# Bridge.net
KiCad netlist of a schematic drawn in Altium Designer
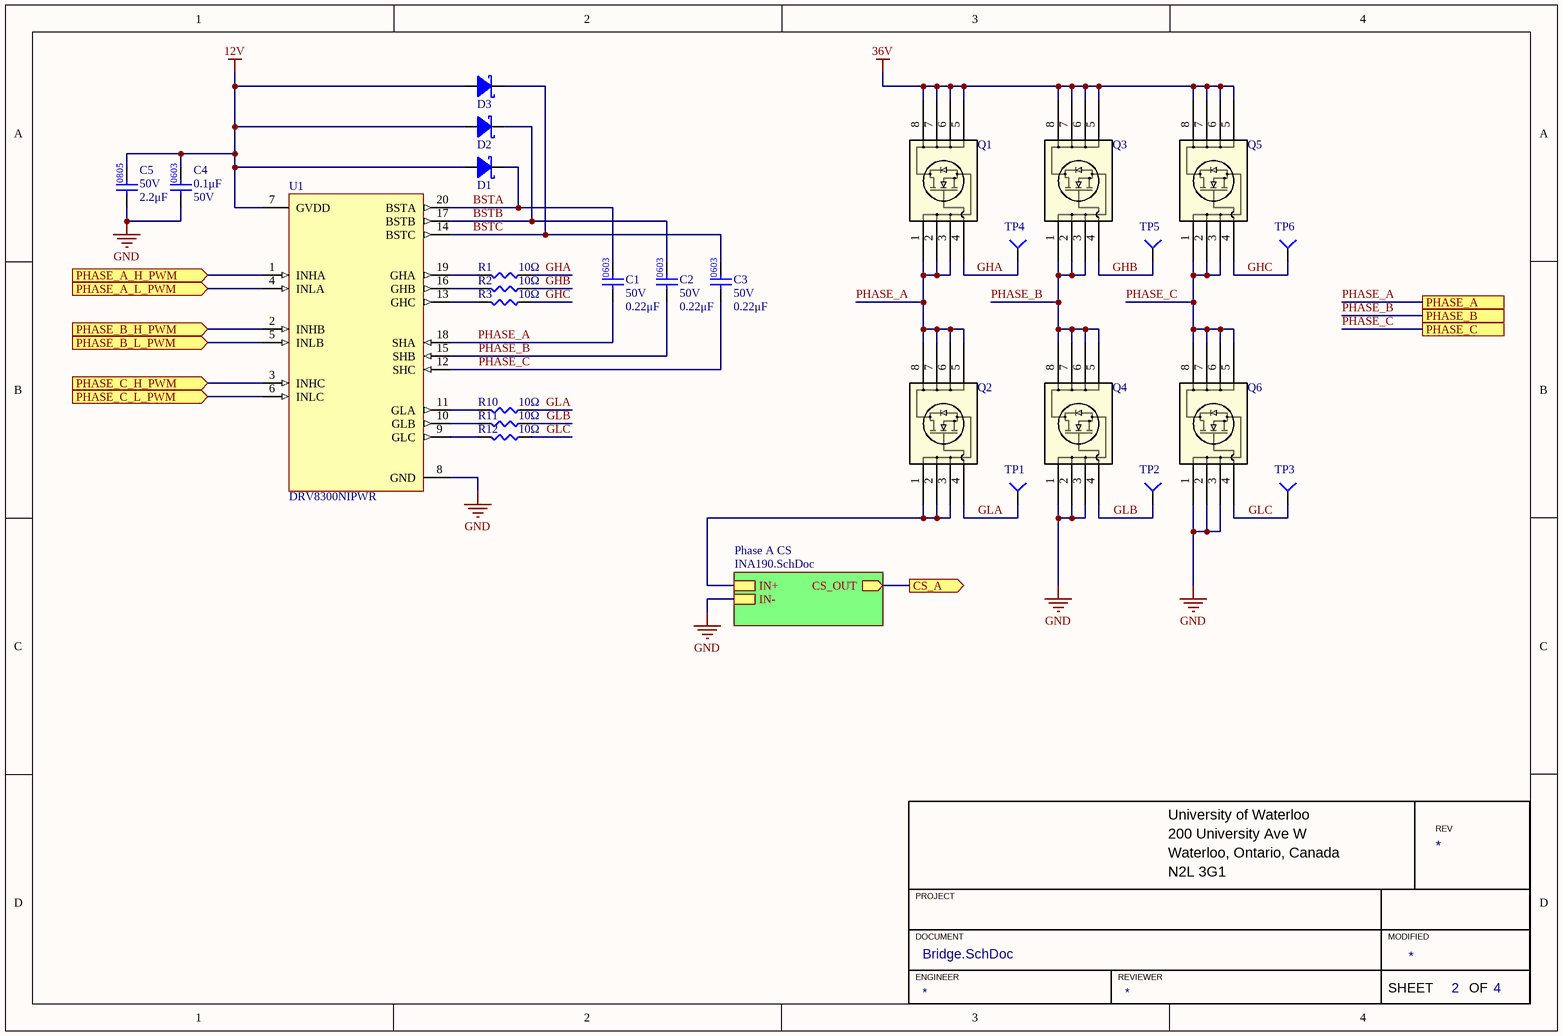
[diagram p0: Bridge.SchDoc]

(export (version "E")
  (design (tool "Eeschema 10.0.6"))
  (components
    (comp (ref "C1")
      (value "0.22μF")
      (footprint "CAP0603")
      (description "CAP CER 0.22UF 50V X7R 0603")
      (fields
        (field (name "VOLTAGE RATING") "50V")
        (field (name "LCSC PART #") "C5378")
        (field (name "Comment") "CAP_0.22uF_50V_0603")
      )
      (libsource (lib "UWRT_Schematic_Library_2020") (part "CAP_0.22uF_50V_0603"))
    )
    (comp (ref "C2")
      (value "0.22μF")
      (footprint "CAP0603")
      (description "CAP CER 0.22UF 50V X7R 0603")
      (fields
        (field (name "VOLTAGE RATING") "50V")
        (field (name "LCSC PART #") "C5378")
        (field (name "Comment") "CAP_0.22uF_50V_0603")
      )
      (libsource (lib "UWRT_Schematic_Library_2020") (part "CAP_0.22uF_50V_0603"))
    )
    (comp (ref "C3")
      (value "0.22μF")
      (footprint "CAP0603")
      (description "CAP CER 0.22UF 50V X7R 0603")
      (fields
        (field (name "VOLTAGE RATING") "50V")
        (field (name "LCSC PART #") "C5378")
        (field (name "Comment") "CAP_0.22uF_50V_0603")
      )
      (libsource (lib "UWRT_Schematic_Library_2020") (part "CAP_0.22uF_50V_0603"))
    )
    (comp (ref "C4")
      (value "0.1μF")
      (footprint "CAP0603")
      (description "CAP CER 0.1UF 50V X7R 0603")
      (fields (field (name "VOLTAGE RATING") "50V") (field (name "Comment") "CAP_0.1uF_50V_0603"))
      (libsource (lib "UWRT_Schematic_Library_2020") (part "CAP_0.1uF_50V_0603"))
    )
    (comp (ref "C5")
      (value "2.2μF")
      (footprint "CAP0805")
      (description "CAP CER 2.2UF 50V X5R 0805")
      (fields (field (name "VOLTAGE RATING") "50V") (field (name "Comment") "CAP_2.2uF_50V_0805"))
      (libsource (lib "UWRT_Schematic_Library_2020") (part "CAP_2.2uF_50V_0805"))
    )
    (comp (ref "D1")
      (value "DIO_SCHOTTKY_60V_2A")
      (footprint "SOD-123_FLAT")
      (description "DIODE SCHOTTKY 40V 520MA SOD323")
      (libsource (lib "Personal_Schematic_Library_2022") (part "DIO_SCHOTTKY_60V_2A"))
    )
    (comp (ref "D2")
      (value "DIO_SCHOTTKY_60V_2A")
      (footprint "SOD-123_FLAT")
      (description "DIODE SCHOTTKY 40V 520MA SOD323")
      (libsource (lib "Personal_Schematic_Library_2022") (part "DIO_SCHOTTKY_60V_2A"))
    )
    (comp (ref "D3")
      (value "DIO_SCHOTTKY_60V_2A")
      (footprint "SOD-123_FLAT")
      (description "DIODE SCHOTTKY 40V 520MA SOD323")
      (libsource (lib "Personal_Schematic_Library_2022") (part "DIO_SCHOTTKY_60V_2A"))
    )
    (comp (ref "Q1")
      (value "CSD19502Q5B")
      (footprint "DFN5060")
      (description "MOSFET N-CH 80V 100A 8VSON")
      (libsource (lib "UWRT_Schematic_Library_2020") (part "NMOS_CSD19502Q5B_80V_100A"))
    )
    (comp (ref "Q2")
      (value "CSD19502Q5B")
      (footprint "DFN5060")
      (description "MOSFET N-CH 80V 100A 8VSON")
      (libsource (lib "UWRT_Schematic_Library_2020") (part "NMOS_CSD19502Q5B_80V_100A"))
    )
    (comp (ref "Q3")
      (value "CSD19502Q5B")
      (footprint "DFN5060")
      (description "MOSFET N-CH 80V 100A 8VSON")
      (libsource (lib "UWRT_Schematic_Library_2020") (part "NMOS_CSD19502Q5B_80V_100A"))
    )
    (comp (ref "Q4")
      (value "CSD19502Q5B")
      (footprint "DFN5060")
      (description "MOSFET N-CH 80V 100A 8VSON")
      (libsource (lib "UWRT_Schematic_Library_2020") (part "NMOS_CSD19502Q5B_80V_100A"))
    )
    (comp (ref "Q5")
      (value "CSD19502Q5B")
      (footprint "DFN5060")
      (description "MOSFET N-CH 80V 100A 8VSON")
      (libsource (lib "UWRT_Schematic_Library_2020") (part "NMOS_CSD19502Q5B_80V_100A"))
    )
    (comp (ref "Q6")
      (value "CSD19502Q5B")
      (footprint "DFN5060")
      (description "MOSFET N-CH 80V 100A 8VSON")
      (libsource (lib "UWRT_Schematic_Library_2020") (part "NMOS_CSD19502Q5B_80V_100A"))
    )
    (comp (ref "R1")
      (value "10Ω")
      (footprint "RES0805")
      (description "RES 10 OHM 1% 1/8W 0805")
      (fields (field (name "LCSC PART #") "C17415") (field (name "Comment") "RES_10Ω_0805_1%"))
      (libsource (lib "UWRT_Schematic_Library_2020") (part "RES_10Ω_0805_1%"))
    )
    (comp (ref "R2")
      (value "10Ω")
      (footprint "RES0805")
      (description "RES 10 OHM 1% 1/8W 0805")
      (fields (field (name "LCSC PART #") "C17415") (field (name "Comment") "RES_10Ω_0805_1%"))
      (libsource (lib "UWRT_Schematic_Library_2020") (part "RES_10Ω_0805_1%"))
    )
    (comp (ref "R3")
      (value "10Ω")
      (footprint "RES0805")
      (description "RES 10 OHM 1% 1/8W 0805")
      (fields (field (name "LCSC PART #") "C17415") (field (name "Comment") "RES_10Ω_0805_1%"))
      (libsource (lib "UWRT_Schematic_Library_2020") (part "RES_10Ω_0805_1%"))
    )
    (comp (ref "R10")
      (value "10Ω")
      (footprint "RES0805")
      (description "RES 10 OHM 1% 1/8W 0805")
      (fields (field (name "LCSC PART #") "C17415") (field (name "Comment") "RES_10Ω_0805_1%"))
      (libsource (lib "UWRT_Schematic_Library_2020") (part "RES_10Ω_0805_1%"))
    )
    (comp (ref "R11")
      (value "10Ω")
      (footprint "RES0805")
      (description "RES 10 OHM 1% 1/8W 0805")
      (fields (field (name "LCSC PART #") "C17415") (field (name "Comment") "RES_10Ω_0805_1%"))
      (libsource (lib "UWRT_Schematic_Library_2020") (part "RES_10Ω_0805_1%"))
    )
    (comp (ref "R12")
      (value "10Ω")
      (footprint "RES0805")
      (description "RES 10 OHM 1% 1/8W 0805")
      (fields (field (name "LCSC PART #") "C17415") (field (name "Comment") "RES_10Ω_0805_1%"))
      (libsource (lib "UWRT_Schematic_Library_2020") (part "RES_10Ω_0805_1%"))
    )
    (comp (ref "TP1")
      (value "TESTPOINT_1MM_CIRCLE")
      (footprint "TESTPOINT_CIRCLE_1MM")
      (description "TESTPOINT 1MM CIRCLE")
      (libsource (lib "UWRT_Schematic_Library_2020") (part "TESTPOINT_1MM_CIRCLE"))
    )
    (comp (ref "TP2")
      (value "TESTPOINT_1MM_CIRCLE")
      (footprint "TESTPOINT_CIRCLE_1MM")
      (description "TESTPOINT 1MM CIRCLE")
      (libsource (lib "UWRT_Schematic_Library_2020") (part "TESTPOINT_1MM_CIRCLE"))
    )
    (comp (ref "TP3")
      (value "TESTPOINT_1MM_CIRCLE")
      (footprint "TESTPOINT_CIRCLE_1MM")
      (description "TESTPOINT 1MM CIRCLE")
      (libsource (lib "UWRT_Schematic_Library_2020") (part "TESTPOINT_1MM_CIRCLE"))
    )
    (comp (ref "TP4")
      (value "TESTPOINT_1MM_CIRCLE")
      (footprint "TESTPOINT_CIRCLE_1MM")
      (description "TESTPOINT 1MM CIRCLE")
      (libsource (lib "UWRT_Schematic_Library_2020") (part "TESTPOINT_1MM_CIRCLE"))
    )
    (comp (ref "TP5")
      (value "TESTPOINT_1MM_CIRCLE")
      (footprint "TESTPOINT_CIRCLE_1MM")
      (description "TESTPOINT 1MM CIRCLE")
      (libsource (lib "UWRT_Schematic_Library_2020") (part "TESTPOINT_1MM_CIRCLE"))
    )
    (comp (ref "TP6")
      (value "TESTPOINT_1MM_CIRCLE")
      (footprint "TESTPOINT_CIRCLE_1MM")
      (description "TESTPOINT 1MM CIRCLE")
      (libsource (lib "UWRT_Schematic_Library_2020") (part "TESTPOINT_1MM_CIRCLE"))
    )
    (comp (ref "U1")
      (value "DRV8300NIPWR")
      (footprint "20-TSSOP_4400X6500X1200")
      (description "100-V MAX SIMPLE 3-PHASE GATE DR")
      (fields (field (name "MANUFACTURER PART NUMBER 1") "DRV8300NIPWR"))
      (libsource (lib "UWRT_Schematic_Library_2020") (part "DRV8300NIPWR"))
    )
  )
  (nets
    (net (code "1") (name "/BSTA") (class "Default")
      (node (ref "C1") (pin "2") (pinfunction "2_2") (pintype "passive"))
      (node (ref "D1") (pin "1") (pinfunction "Cathode_1") (pintype "passive"))
      (node (ref "U1") (pin "20") (pinfunction "BSTA_20") (pintype "output"))
    )
    (net (code "2") (name "/BSTB") (class "Default")
      (node (ref "C2") (pin "2") (pinfunction "2_2") (pintype "passive"))
      (node (ref "D2") (pin "1") (pinfunction "Cathode_1") (pintype "passive"))
      (node (ref "U1") (pin "17") (pinfunction "BSTB_17") (pintype "output"))
    )
    (net (code "3") (name "/BSTC") (class "Default")
      (node (ref "C3") (pin "2") (pinfunction "2_2") (pintype "passive"))
      (node (ref "D3") (pin "1") (pinfunction "Cathode_1") (pintype "passive"))
      (node (ref "U1") (pin "14") (pinfunction "BSTC_14") (pintype "output"))
    )
    (net (code "5") (name "/GHA") (class "Default")
      (node (ref "Q1") (pin "4") (pinfunction "G_4") (pintype "passive"))
      (node (ref "R1") (pin "2") (pinfunction "2_2") (pintype "passive"))
      (node (ref "TP4") (pin "1") (pinfunction "=value_1") (pintype "passive"))
    )
    (net (code "6") (name "/GHB") (class "Default")
      (node (ref "Q3") (pin "4") (pinfunction "G_4") (pintype "passive"))
      (node (ref "R2") (pin "2") (pinfunction "2_2") (pintype "passive"))
      (node (ref "TP5") (pin "1") (pinfunction "=value_1") (pintype "passive"))
    )
    (net (code "7") (name "/GHC") (class "Default")
      (node (ref "Q5") (pin "4") (pinfunction "G_4") (pintype "passive"))
      (node (ref "R3") (pin "2") (pinfunction "2_2") (pintype "passive"))
      (node (ref "TP6") (pin "1") (pinfunction "=value_1") (pintype "passive"))
    )
    (net (code "8") (name "/GLA") (class "Default")
      (node (ref "Q2") (pin "4") (pinfunction "G_4") (pintype "passive"))
      (node (ref "R10") (pin "2") (pinfunction "2_2") (pintype "passive"))
      (node (ref "TP1") (pin "1") (pinfunction "=value_1") (pintype "passive"))
    )
    (net (code "9") (name "/GLB") (class "Default")
      (node (ref "Q4") (pin "4") (pinfunction "G_4") (pintype "passive"))
      (node (ref "R11") (pin "2") (pinfunction "2_2") (pintype "passive"))
      (node (ref "TP2") (pin "1") (pinfunction "=value_1") (pintype "passive"))
    )
    (net (code "10") (name "/GLC") (class "Default")
      (node (ref "Q6") (pin "4") (pinfunction "G_4") (pintype "passive"))
      (node (ref "R12") (pin "2") (pinfunction "2_2") (pintype "passive"))
      (node (ref "TP3") (pin "1") (pinfunction "=value_1") (pintype "passive"))
    )
    (net (code "11") (name "/IN+") (class "Default")
      (node (ref "Q2") (pin "1") (pinfunction "S_1") (pintype "passive"))
      (node (ref "Q2") (pin "2") (pinfunction "S_2") (pintype "passive"))
      (node (ref "Q2") (pin "3") (pinfunction "S_3") (pintype "passive"))
    )
    (net (code "12") (name "/PHASE_A") (class "Default")
      (node (ref "C1") (pin "1") (pinfunction "1_1") (pintype "passive"))
      (node (ref "Q1") (pin "1") (pinfunction "S_1") (pintype "passive"))
      (node (ref "Q1") (pin "2") (pinfunction "S_2") (pintype "passive"))
      (node (ref "Q1") (pin "3") (pinfunction "S_3") (pintype "passive"))
      (node (ref "Q2") (pin "5") (pinfunction "D_5") (pintype "passive"))
      (node (ref "Q2") (pin "6") (pinfunction "D_6") (pintype "passive"))
      (node (ref "Q2") (pin "7") (pinfunction "D_7") (pintype "passive"))
      (node (ref "Q2") (pin "8") (pinfunction "D_8") (pintype "passive"))
      (node (ref "U1") (pin "18") (pinfunction "SHA_18") (pintype "input"))
    )
    (net (code "13") (name "/PHASE_A_H_PWM") (class "Default")
      (node (ref "U1") (pin "1") (pinfunction "INHA_1") (pintype "input"))
    )
    (net (code "14") (name "/PHASE_A_L_PWM") (class "Default")
      (node (ref "U1") (pin "4") (pinfunction "INLA_4") (pintype "input"))
    )
    (net (code "15") (name "/PHASE_B") (class "Default")
      (node (ref "C2") (pin "1") (pinfunction "1_1") (pintype "passive"))
      (node (ref "Q3") (pin "1") (pinfunction "S_1") (pintype "passive"))
      (node (ref "Q3") (pin "2") (pinfunction "S_2") (pintype "passive"))
      (node (ref "Q3") (pin "3") (pinfunction "S_3") (pintype "passive"))
      (node (ref "Q4") (pin "5") (pinfunction "D_5") (pintype "passive"))
      (node (ref "Q4") (pin "6") (pinfunction "D_6") (pintype "passive"))
      (node (ref "Q4") (pin "7") (pinfunction "D_7") (pintype "passive"))
      (node (ref "Q4") (pin "8") (pinfunction "D_8") (pintype "passive"))
      (node (ref "U1") (pin "15") (pinfunction "SHB_15") (pintype "input"))
    )
    (net (code "16") (name "/PHASE_B_H_PWM") (class "Default")
      (node (ref "U1") (pin "2") (pinfunction "INHB_2") (pintype "input"))
    )
    (net (code "17") (name "/PHASE_B_L_PWM") (class "Default")
      (node (ref "U1") (pin "5") (pinfunction "INLB_5") (pintype "input"))
    )
    (net (code "18") (name "/PHASE_C") (class "Default")
      (node (ref "C3") (pin "1") (pinfunction "1_1") (pintype "passive"))
      (node (ref "Q5") (pin "1") (pinfunction "S_1") (pintype "passive"))
      (node (ref "Q5") (pin "2") (pinfunction "S_2") (pintype "passive"))
      (node (ref "Q5") (pin "3") (pinfunction "S_3") (pintype "passive"))
      (node (ref "Q6") (pin "5") (pinfunction "D_5") (pintype "passive"))
      (node (ref "Q6") (pin "6") (pinfunction "D_6") (pintype "passive"))
      (node (ref "Q6") (pin "7") (pinfunction "D_7") (pintype "passive"))
      (node (ref "Q6") (pin "8") (pinfunction "D_8") (pintype "passive"))
      (node (ref "U1") (pin "12") (pinfunction "SHC_12") (pintype "input"))
    )
    (net (code "19") (name "/PHASE_C_H_PWM") (class "Default")
      (node (ref "U1") (pin "3") (pinfunction "INHC_3") (pintype "input"))
    )
    (net (code "20") (name "/PHASE_C_L_PWM") (class "Default")
      (node (ref "U1") (pin "6") (pinfunction "INLC_6") (pintype "input"))
    )
    (net (code "21") (name "12V") (class "Default")
      (node (ref "C4") (pin "2") (pinfunction "2_2") (pintype "passive"))
      (node (ref "C5") (pin "2") (pinfunction "2_2") (pintype "passive"))
      (node (ref "D1") (pin "2") (pinfunction "Anode_2") (pintype "passive"))
      (node (ref "D2") (pin "2") (pinfunction "Anode_2") (pintype "passive"))
      (node (ref "D3") (pin "2") (pinfunction "Anode_2") (pintype "passive"))
      (node (ref "U1") (pin "7") (pinfunction "GVDD_7") (pintype "power_in"))
    )
    (net (code "22") (name "36V") (class "Default")
      (node (ref "Q1") (pin "5") (pinfunction "D_5") (pintype "passive"))
      (node (ref "Q1") (pin "6") (pinfunction "D_6") (pintype "passive"))
      (node (ref "Q1") (pin "7") (pinfunction "D_7") (pintype "passive"))
      (node (ref "Q1") (pin "8") (pinfunction "D_8") (pintype "passive"))
      (node (ref "Q3") (pin "5") (pinfunction "D_5") (pintype "passive"))
      (node (ref "Q3") (pin "6") (pinfunction "D_6") (pintype "passive"))
      (node (ref "Q3") (pin "7") (pinfunction "D_7") (pintype "passive"))
      (node (ref "Q3") (pin "8") (pinfunction "D_8") (pintype "passive"))
      (node (ref "Q5") (pin "5") (pinfunction "D_5") (pintype "passive"))
      (node (ref "Q5") (pin "6") (pinfunction "D_6") (pintype "passive"))
      (node (ref "Q5") (pin "7") (pinfunction "D_7") (pintype "passive"))
      (node (ref "Q5") (pin "8") (pinfunction "D_8") (pintype "passive"))
    )
    (net (code "23") (name "GND") (class "Default")
      (node (ref "C4") (pin "1") (pinfunction "1_1") (pintype "passive"))
      (node (ref "C5") (pin "1") (pinfunction "1_1") (pintype "passive"))
      (node (ref "Q4") (pin "1") (pinfunction "S_1") (pintype "passive"))
      (node (ref "Q4") (pin "2") (pinfunction "S_2") (pintype "passive"))
      (node (ref "Q4") (pin "3") (pinfunction "S_3") (pintype "passive"))
      (node (ref "Q6") (pin "1") (pinfunction "S_1") (pintype "passive"))
      (node (ref "Q6") (pin "2") (pinfunction "S_2") (pintype "passive"))
      (node (ref "Q6") (pin "3") (pinfunction "S_3") (pintype "passive"))
      (node (ref "U1") (pin "8") (pinfunction "GND_8") (pintype "passive"))
    )
    (net (code "24") (name "Net-(U1-GHA)") (class "Default")
      (node (ref "R1") (pin "1") (pinfunction "1_1") (pintype "passive"))
      (node (ref "U1") (pin "19") (pinfunction "GHA_19") (pintype "output"))
    )
    (net (code "25") (name "Net-(U1-GHB)") (class "Default")
      (node (ref "R2") (pin "1") (pinfunction "1_1") (pintype "passive"))
      (node (ref "U1") (pin "16") (pinfunction "GHB_16") (pintype "output"))
    )
    (net (code "26") (name "Net-(U1-GHC)") (class "Default")
      (node (ref "R3") (pin "1") (pinfunction "1_1") (pintype "passive"))
      (node (ref "U1") (pin "13") (pinfunction "GHC_13") (pintype "output"))
    )
    (net (code "27") (name "Net-(U1-GLA)") (class "Default")
      (node (ref "R10") (pin "1") (pinfunction "1_1") (pintype "passive"))
      (node (ref "U1") (pin "11") (pinfunction "GLA_11") (pintype "output"))
    )
    (net (code "28") (name "Net-(U1-GLB)") (class "Default")
      (node (ref "R11") (pin "1") (pinfunction "1_1") (pintype "passive"))
      (node (ref "U1") (pin "10") (pinfunction "GLB_10") (pintype "output"))
    )
    (net (code "29") (name "Net-(U1-GLC)") (class "Default")
      (node (ref "R12") (pin "1") (pinfunction "1_1") (pintype "passive"))
      (node (ref "U1") (pin "9") (pinfunction "GLC_9") (pintype "output"))
    )
  )
)
